# ProtoShield-v26.net
KiCad netlist of a schematic drawn in EAGLE
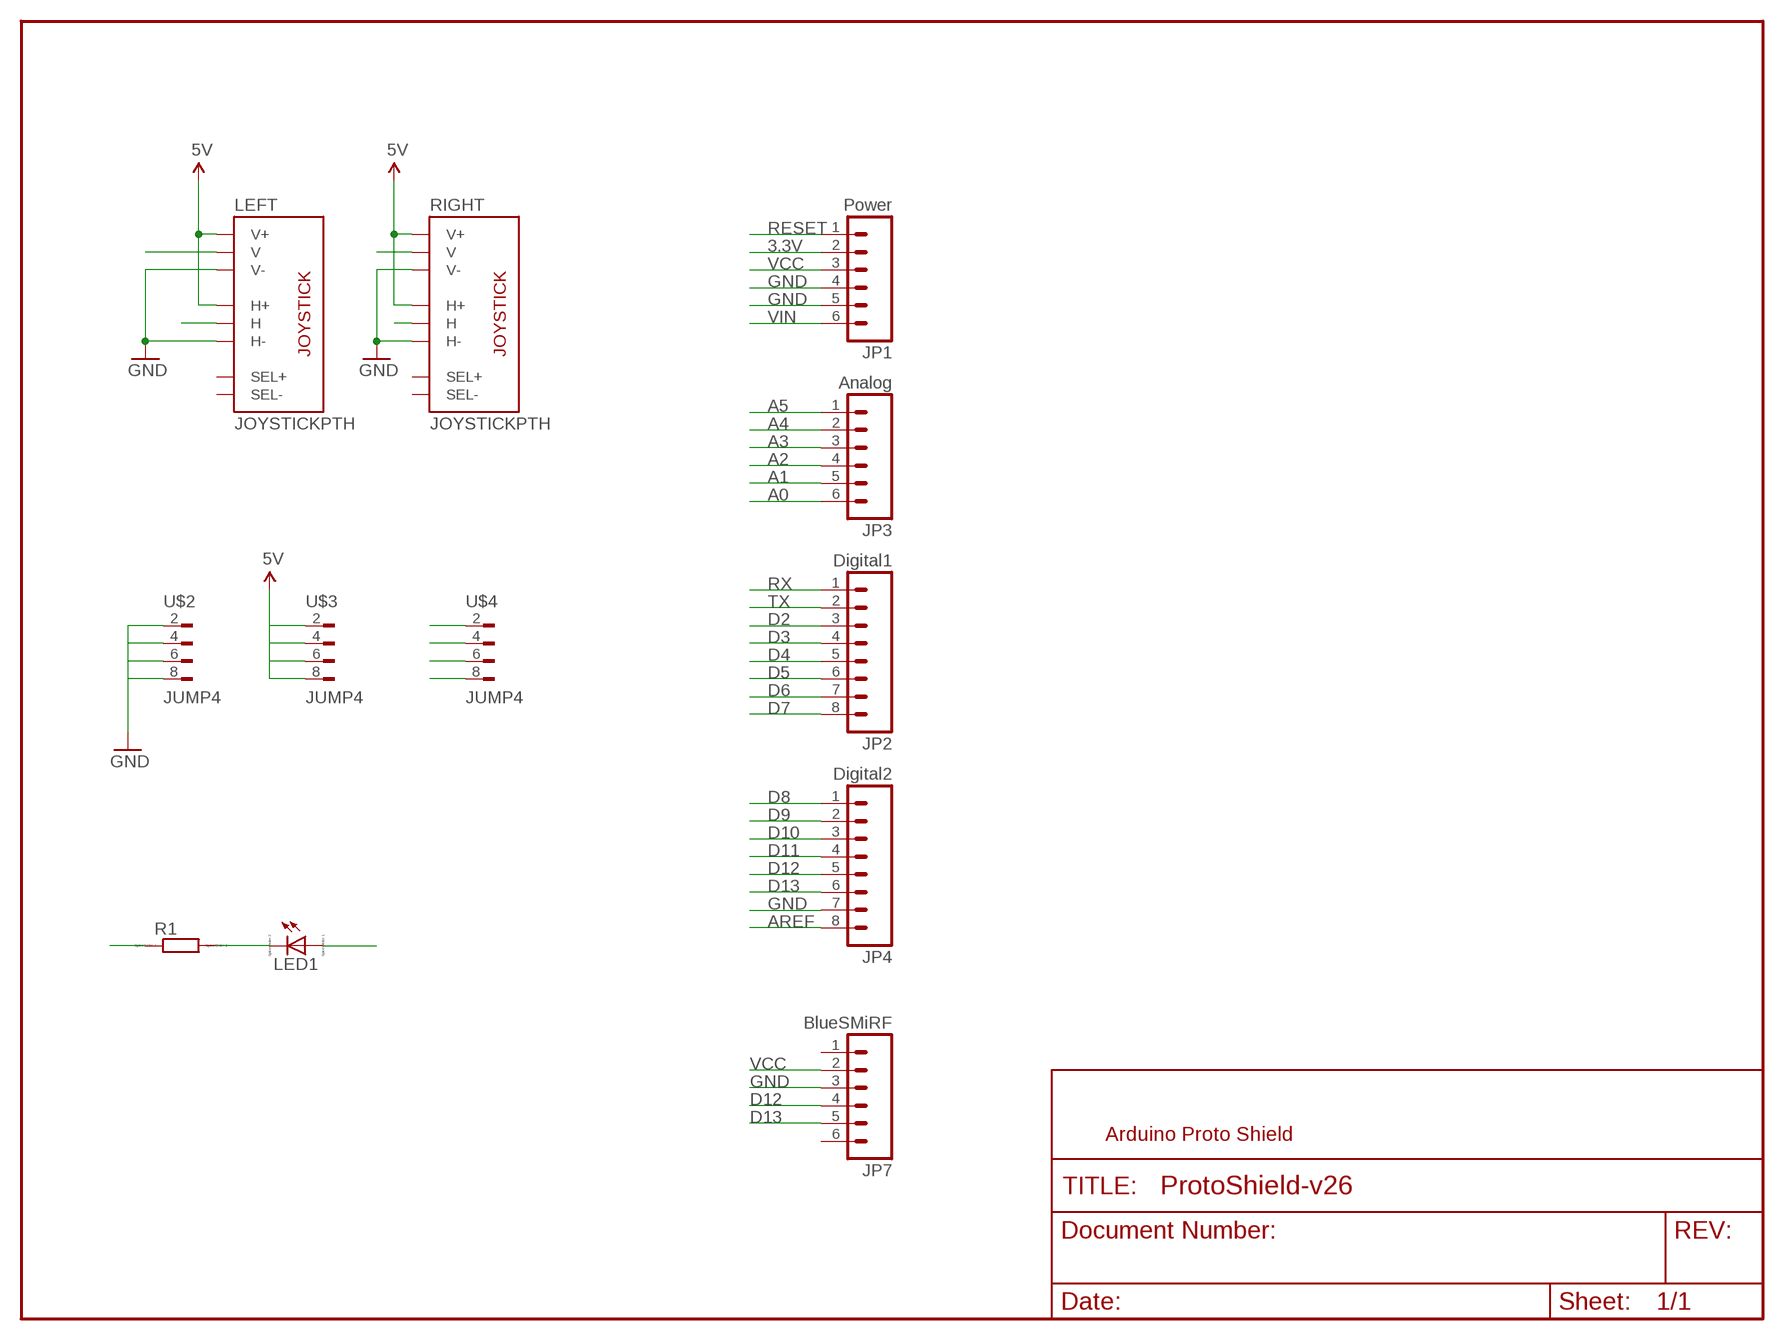
[diagram p0: schematic, sheet 1]

(export (version "E")
  (design (tool "Eeschema 10.0.6"))
  (components
    (comp (ref "JP1")
      (value "Power")
      (footprint "eagle-import:1X06")
      (libsource (lib "eagle-import") (part "M06SIP"))
    )
    (comp (ref "JP2")
      (value "Digital1")
      (footprint "eagle-import:1X08")
      (libsource (lib "eagle-import") (part "M08"))
    )
    (comp (ref "JP3")
      (value "Analog")
      (footprint "eagle-import:1X06")
      (libsource (lib "eagle-import") (part "M06SIP"))
    )
    (comp (ref "JP4")
      (value "Digital2")
      (footprint "eagle-import:1X08")
      (libsource (lib "eagle-import") (part "M08"))
    )
    (comp (ref "JP7")
      (value "BlueSMiRF")
      (footprint "eagle-import:1X06")
      (libsource (lib "eagle-import") (part "M06SIP"))
    )
    (comp (ref "LED1")
      (value "LED_ELD260")
      (footprint "eagle-import:LED_LD260")
      (libsource (lib "eagle-import") (part "LED_ELD260"))
    )
    (comp (ref "LEFT")
      (value "JOYSTICKPTH")
      (footprint "eagle-import:JOYSTICK")
      (libsource (lib "eagle-import") (part "JOYSTICKPTH"))
    )
    (comp (ref "R1")
      (value "R0204/7")
      (footprint "eagle-import:0204_7")
      (libsource (lib "eagle-import") (part "R0204/7"))
    )
    (comp (ref "RIGHT")
      (value "JOYSTICKPTH")
      (footprint "eagle-import:JOYSTICK")
      (libsource (lib "eagle-import") (part "JOYSTICKPTH"))
    )
    (comp (ref "U$2")
      (value "JUMP4")
      (footprint "eagle-import:JUMP4")
      (libsource (lib "eagle-import") (part "JUMP4"))
    )
    (comp (ref "U$3")
      (value "JUMP4")
      (footprint "eagle-import:JUMP4")
      (libsource (lib "eagle-import") (part "JUMP4"))
    )
    (comp (ref "U$4")
      (value "JUMP4")
      (footprint "eagle-import:JUMP4")
      (libsource (lib "eagle-import") (part "JUMP4"))
    )
  )
  (nets
    (net (code "1") (name "/3.3V") (class "Default")
      (node (ref "JP1") (pin "2") (pinfunction "2_2") (pintype "passive"))
    )
    (net (code "2") (name "/A0") (class "Default")
      (node (ref "JP3") (pin "6") (pinfunction "6_6") (pintype "passive"))
      (node (ref "RIGHT") (pin "H2") (pinfunction "H_H2") (pintype "bidirectional"))
    )
    (net (code "3") (name "/A1") (class "Default")
      (node (ref "JP3") (pin "5") (pinfunction "5_5") (pintype "passive"))
      (node (ref "RIGHT") (pin "V2") (pinfunction "V_V2") (pintype "bidirectional"))
    )
    (net (code "4") (name "/A2") (class "Default")
      (node (ref "JP3") (pin "4") (pinfunction "4_4") (pintype "passive"))
      (node (ref "LEFT") (pin "V2") (pinfunction "V_V2") (pintype "bidirectional"))
    )
    (net (code "5") (name "/A3") (class "Default")
      (node (ref "JP3") (pin "3") (pinfunction "3_3") (pintype "passive"))
      (node (ref "LEFT") (pin "H2") (pinfunction "H_H2") (pintype "bidirectional"))
    )
    (net (code "6") (name "/A4") (class "Default")
      (node (ref "JP3") (pin "2") (pinfunction "2_2") (pintype "passive"))
    )
    (net (code "7") (name "/A5") (class "Default")
      (node (ref "JP3") (pin "1") (pinfunction "1_1") (pintype "passive"))
    )
    (net (code "8") (name "/AREF") (class "Default")
      (node (ref "JP4") (pin "8") (pinfunction "8_8") (pintype "passive"))
    )
    (net (code "9") (name "/D2") (class "Default")
      (node (ref "JP2") (pin "3") (pinfunction "3_3") (pintype "passive"))
    )
    (net (code "10") (name "/D3") (class "Default")
      (node (ref "JP2") (pin "4") (pinfunction "4_4") (pintype "passive"))
      (node (ref "LED1") (pin "A") (pinfunction "A_A") (pintype "passive"))
    )
    (net (code "11") (name "/D4") (class "Default")
      (node (ref "JP2") (pin "5") (pinfunction "5_5") (pintype "passive"))
    )
    (net (code "12") (name "/D5") (class "Default")
      (node (ref "JP2") (pin "6") (pinfunction "6_6") (pintype "passive"))
      (node (ref "U$4") (pin "2") (pinfunction "1_2") (pintype "passive"))
    )
    (net (code "13") (name "/D6") (class "Default")
      (node (ref "JP2") (pin "7") (pinfunction "7_7") (pintype "passive"))
    )
    (net (code "14") (name "/D7") (class "Default")
      (node (ref "JP2") (pin "8") (pinfunction "8_8") (pintype "passive"))
    )
    (net (code "15") (name "/D8") (class "Default")
      (node (ref "JP4") (pin "1") (pinfunction "1_1") (pintype "passive"))
    )
    (net (code "16") (name "/D9") (class "Default")
      (node (ref "JP4") (pin "2") (pinfunction "2_2") (pintype "passive"))
      (node (ref "U$4") (pin "4") (pinfunction "2_4") (pintype "passive"))
    )
    (net (code "17") (name "/D10") (class "Default")
      (node (ref "JP4") (pin "3") (pinfunction "3_3") (pintype "passive"))
      (node (ref "U$4") (pin "6") (pinfunction "3_6") (pintype "passive"))
    )
    (net (code "18") (name "/D11") (class "Default")
      (node (ref "JP4") (pin "4") (pinfunction "4_4") (pintype "passive"))
      (node (ref "U$4") (pin "8") (pinfunction "4_8") (pintype "passive"))
    )
    (net (code "19") (name "/D12") (class "Default")
      (node (ref "JP4") (pin "5") (pinfunction "5_5") (pintype "passive"))
      (node (ref "JP7") (pin "4") (pinfunction "4_4") (pintype "passive"))
    )
    (net (code "20") (name "/D13") (class "Default")
      (node (ref "JP4") (pin "6") (pinfunction "6_6") (pintype "passive"))
      (node (ref "JP7") (pin "5") (pinfunction "5_5") (pintype "passive"))
    )
    (net (code "21") (name "/RESET") (class "Default")
      (node (ref "JP1") (pin "1") (pinfunction "1_1") (pintype "passive"))
    )
    (net (code "22") (name "/RX") (class "Default")
      (node (ref "JP2") (pin "1") (pinfunction "1_1") (pintype "passive"))
    )
    (net (code "23") (name "/TX") (class "Default")
      (node (ref "JP2") (pin "2") (pinfunction "2_2") (pintype "passive"))
    )
    (net (code "24") (name "/VIN") (class "Default")
      (node (ref "JP1") (pin "6") (pinfunction "6_6") (pintype "passive"))
    )
    (net (code "25") (name "5V") (class "Default")
      (node (ref "JP1") (pin "3") (pinfunction "3_3") (pintype "passive"))
      (node (ref "JP7") (pin "2") (pinfunction "2_2") (pintype "passive"))
      (node (ref "LEFT") (pin "H1") (pinfunction "H+_H1") (pintype "bidirectional"))
      (node (ref "LEFT") (pin "V1") (pinfunction "V+_V1") (pintype "bidirectional"))
      (node (ref "RIGHT") (pin "H1") (pinfunction "H+_H1") (pintype "bidirectional"))
      (node (ref "RIGHT") (pin "V1") (pinfunction "V+_V1") (pintype "bidirectional"))
      (node (ref "U$3") (pin "2") (pinfunction "1_2") (pintype "passive"))
      (node (ref "U$3") (pin "4") (pinfunction "2_4") (pintype "passive"))
      (node (ref "U$3") (pin "6") (pinfunction "3_6") (pintype "passive"))
      (node (ref "U$3") (pin "8") (pinfunction "4_8") (pintype "passive"))
    )
    (net (code "26") (name "GND") (class "Default")
      (node (ref "JP1") (pin "4") (pinfunction "4_4") (pintype "passive"))
      (node (ref "JP1") (pin "5") (pinfunction "5_5") (pintype "passive"))
      (node (ref "JP4") (pin "7") (pinfunction "7_7") (pintype "passive"))
      (node (ref "JP7") (pin "3") (pinfunction "3_3") (pintype "passive"))
      (node (ref "LEFT") (pin "H3") (pinfunction "H-_H3") (pintype "bidirectional"))
      (node (ref "LEFT") (pin "V3") (pinfunction "V-_V3") (pintype "bidirectional"))
      (node (ref "R1") (pin "1") (pinfunction "1_1") (pintype "passive"))
      (node (ref "RIGHT") (pin "H3") (pinfunction "H-_H3") (pintype "bidirectional"))
      (node (ref "RIGHT") (pin "V3") (pinfunction "V-_V3") (pintype "bidirectional"))
      (node (ref "U$2") (pin "2") (pinfunction "1_2") (pintype "passive"))
      (node (ref "U$2") (pin "4") (pinfunction "2_4") (pintype "passive"))
      (node (ref "U$2") (pin "6") (pinfunction "3_6") (pintype "passive"))
      (node (ref "U$2") (pin "8") (pinfunction "4_8") (pintype "passive"))
    )
    (net (code "27") (name "Net-(LED1-C)") (class "Default")
      (node (ref "LED1") (pin "K") (pinfunction "C_K") (pintype "passive"))
      (node (ref "R1") (pin "2") (pinfunction "2_2") (pintype "passive"))
    )
    (net (code "28") (name "unconnected-(JP7-Pad1)") (class "Default")
      (node (ref "JP7") (pin "1") (pinfunction "1_1") (pintype "passive"))
    )
    (net (code "29") (name "unconnected-(JP7-Pad6)") (class "Default")
      (node (ref "JP7") (pin "6") (pinfunction "6_6") (pintype "passive"))
    )
    (net (code "30") (name "unconnected-(LEFT-SEL+-PadB1A)") (class "Default")
      (node (ref "LEFT") (pin "B1A") (pinfunction "SEL+_B1A") (pintype "bidirectional"))
    )
    (net (code "31") (name "unconnected-(LEFT-SEL--PadB2A)") (class "Default")
      (node (ref "LEFT") (pin "B2A") (pinfunction "SEL-_B2A") (pintype "bidirectional"))
    )
    (net (code "32") (name "unconnected-(RIGHT-SEL+-PadB1A)") (class "Default")
      (node (ref "RIGHT") (pin "B1A") (pinfunction "SEL+_B1A") (pintype "bidirectional"))
    )
    (net (code "33") (name "unconnected-(RIGHT-SEL--PadB2A)") (class "Default")
      (node (ref "RIGHT") (pin "B2A") (pinfunction "SEL-_B2A") (pintype "bidirectional"))
    )
  )
)
